# Zio_nRF52832_Dev_Board_V1_0.net
KiCad netlist of a schematic drawn in EAGLE
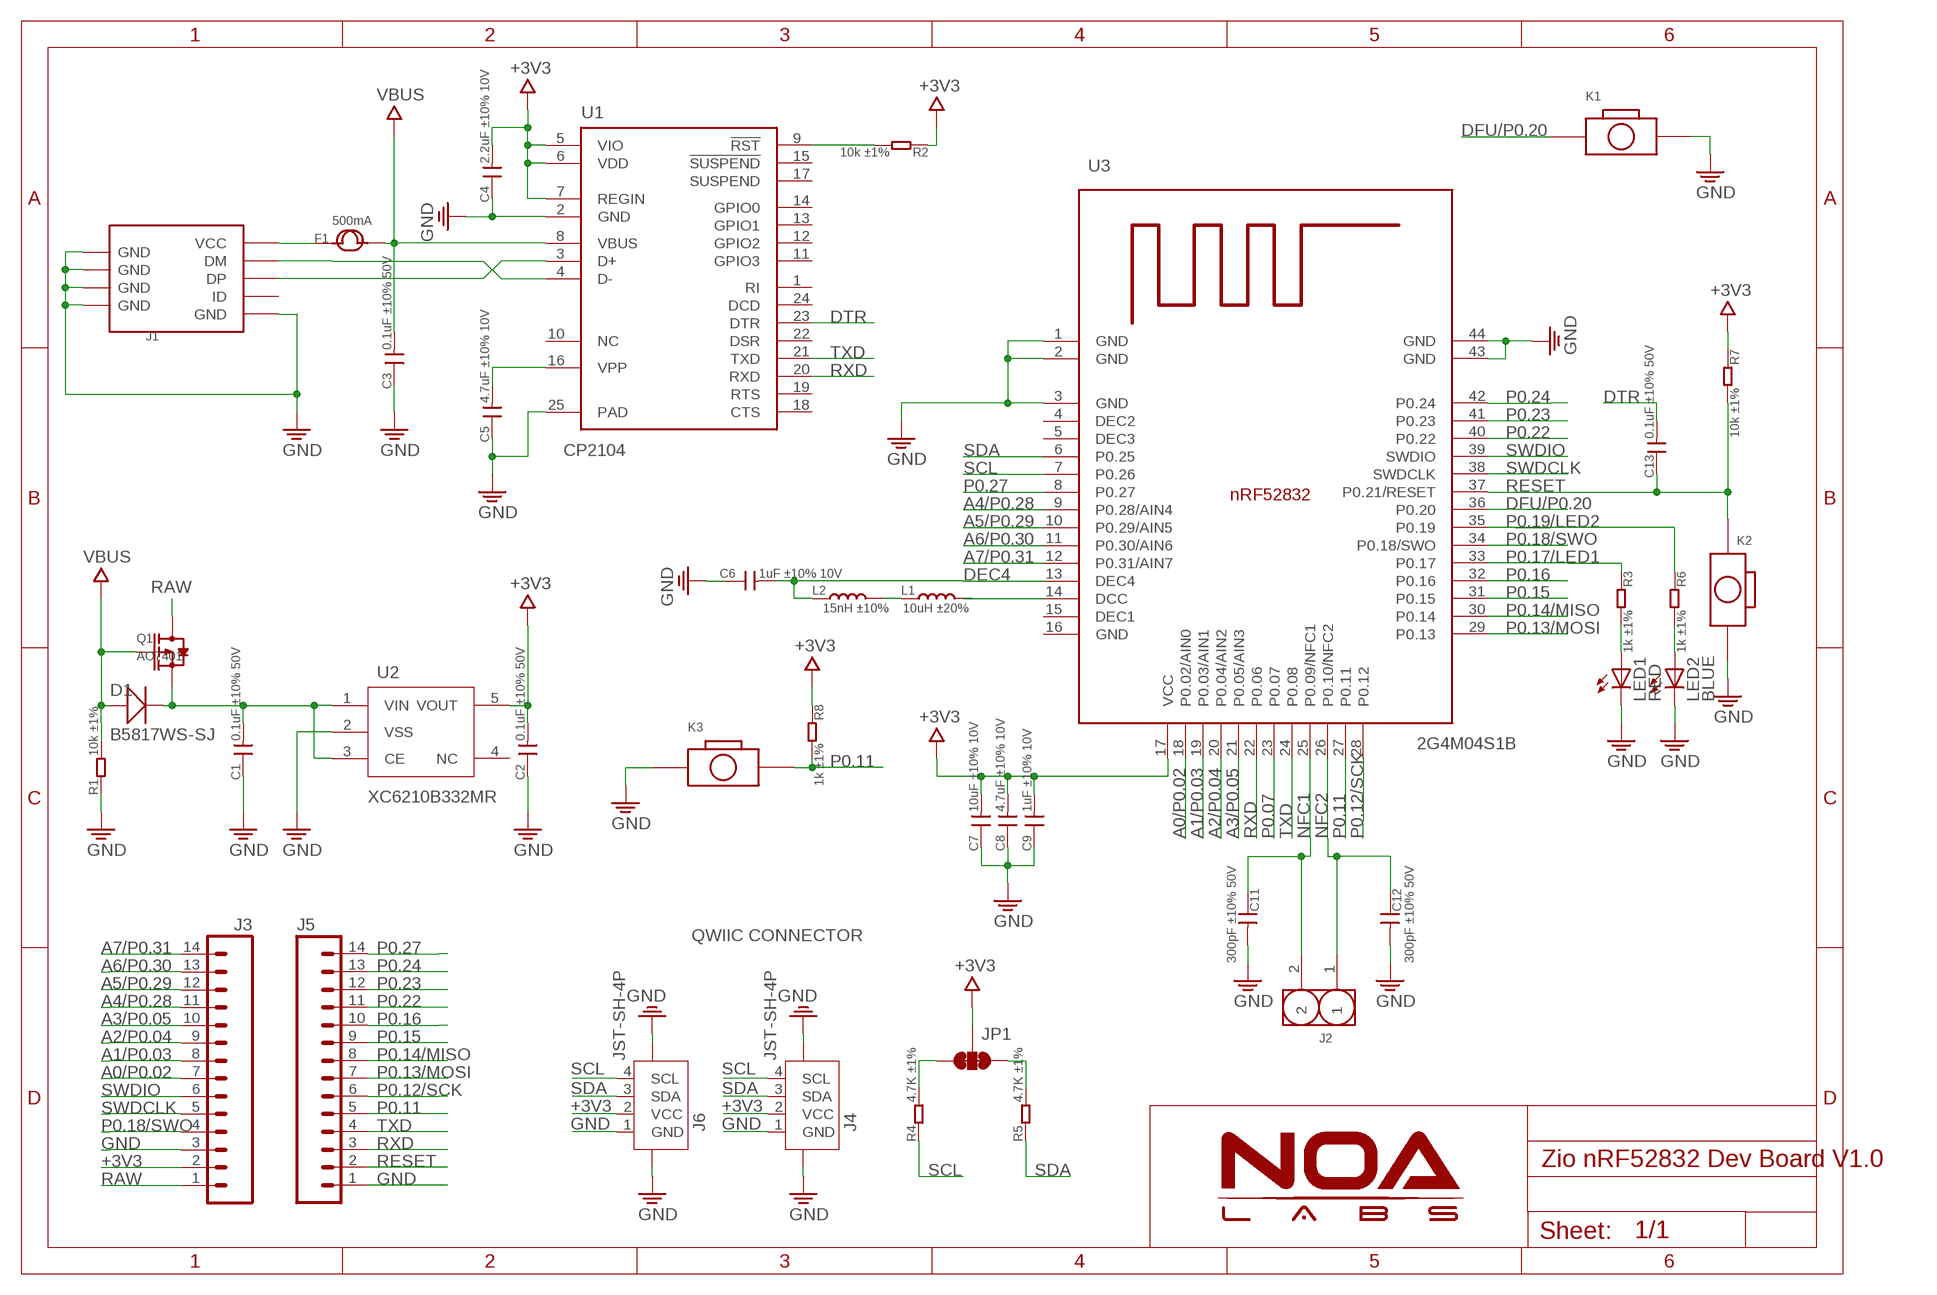
[diagram p0: schematic, sheet 1]

(export (version "E")
  (design (tool "Eeschema 10.0.6"))
  (components
    (comp (ref "C1")
      (value "0.1uF ±10% 50V")
      (footprint "eagle-import:C0603")
      (libsource (lib "eagle-import") (part "C-0603"))
    )
    (comp (ref "C2")
      (value "0.1uF ±10% 50V")
      (footprint "eagle-import:C0603")
      (libsource (lib "eagle-import") (part "C-0603"))
    )
    (comp (ref "C3")
      (value "0.1uF ±10% 50V")
      (footprint "eagle-import:C0603")
      (libsource (lib "eagle-import") (part "C-0603"))
    )
    (comp (ref "C4")
      (value "2.2uF ±10% 10V")
      (footprint "eagle-import:C0603")
      (libsource (lib "eagle-import") (part "C-0603"))
    )
    (comp (ref "C5")
      (value "4.7uF ±10% 10V")
      (footprint "eagle-import:C0603")
      (libsource (lib "eagle-import") (part "C-0603"))
    )
    (comp (ref "C6")
      (value "1uF ±10% 10V")
      (footprint "eagle-import:C0603")
      (libsource (lib "eagle-import") (part "C-0603"))
    )
    (comp (ref "C7")
      (value "10uF ±10% 10V")
      (footprint "eagle-import:C0603")
      (libsource (lib "eagle-import") (part "C-0603"))
    )
    (comp (ref "C8")
      (value "4.7uF ±10% 10V")
      (footprint "eagle-import:C0603")
      (libsource (lib "eagle-import") (part "C-0603"))
    )
    (comp (ref "C9")
      (value "1uF ±10% 10V")
      (footprint "eagle-import:C0603")
      (libsource (lib "eagle-import") (part "C-0603"))
    )
    (comp (ref "C11")
      (value "300pF ±10% 50V")
      (footprint "eagle-import:C0603")
      (libsource (lib "eagle-import") (part "C-0603"))
    )
    (comp (ref "C12")
      (value "300pF ±10% 50V")
      (footprint "eagle-import:C0603")
      (libsource (lib "eagle-import") (part "C-0603"))
    )
    (comp (ref "C13")
      (value "0.1uF ±10% 50V")
      (footprint "eagle-import:C0603")
      (libsource (lib "eagle-import") (part "C-0603"))
    )
    (comp (ref "D1")
      (value "B5817WS-SJ")
      (footprint "eagle-import:SOD323")
      (libsource (lib "eagle-import") (part "D-0805"))
    )
    (comp (ref "F1")
      (value "500mA")
      (footprint "eagle-import:1206")
      (libsource (lib "eagle-import") (part "FUSE1206"))
    )
    (comp (ref "J1")
      (value "USB-MICROE")
      (footprint "eagle-import:MICRO-SMD")
      (libsource (lib "eagle-import") (part "USB-MICROE"))
    )
    (comp (ref "J2")
      (value "HEADER-2P-65/35MIL")
      (footprint "eagle-import:2P-2.54-65_35MIL")
      (libsource (lib "eagle-import") (part "HEADER-2P-65/35MIL"))
    )
    (comp (ref "J3")
      (value "HEADER-14P")
      (footprint "eagle-import:14P-SCREW-2.54")
      (libsource (lib "eagle-import") (part "HEADER-14P"))
    )
    (comp (ref "J4")
      (value "JST-SH-4P")
      (footprint "eagle-import:JST-SH-4P-90")
      (libsource (lib "eagle-import") (part "JST-SH-4P"))
    )
    (comp (ref "J5")
      (value "HEADER-14P")
      (footprint "eagle-import:14P-SCREW-2.54")
      (libsource (lib "eagle-import") (part "HEADER-14P"))
    )
    (comp (ref "J6")
      (value "JST-SH-4P")
      (footprint "eagle-import:JST-SH-4P-90")
      (libsource (lib "eagle-import") (part "JST-SH-4P"))
    )
    (comp (ref "JP1")
      (value "SMT-JUMPER_3_2-NC_TRACE")
      (footprint "eagle-import:SMT-JUMPER_3_2-NC_TRACE")
      (libsource (lib "eagle-import") (part "SMT-JUMPER_3_2-NC_TRACE"))
    )
    (comp (ref "K1")
      (value "BOTTON-2PSKRKAEE020")
      (footprint "eagle-import:SKRKAEE020")
      (libsource (lib "eagle-import") (part "BOTTON-2PSKRKAEE020"))
    )
    (comp (ref "K2")
      (value "BOTTON-2PSKRKAEE020")
      (footprint "eagle-import:SKRKAEE020")
      (libsource (lib "eagle-import") (part "BOTTON-2PSKRKAEE020"))
    )
    (comp (ref "K3")
      (value "BOTTON-2PSKRKAEE020")
      (footprint "eagle-import:SKRKAEE020")
      (libsource (lib "eagle-import") (part "BOTTON-2PSKRKAEE020"))
    )
    (comp (ref "L1")
      (value "10uH ±20%")
      (footprint "eagle-import:L0603")
      (libsource (lib "eagle-import") (part "L-0603"))
    )
    (comp (ref "L2")
      (value "15nH ±10%")
      (footprint "eagle-import:L0402")
      (libsource (lib "eagle-import") (part "L-0402"))
    )
    (comp (ref "LED1")
      (value "RED")
      (footprint "eagle-import:CHIPLED_0603")
      (libsource (lib "eagle-import") (part "LEDCHIPLED_0603"))
    )
    (comp (ref "LED2")
      (value "BLUE")
      (footprint "eagle-import:CHIPLED_0603")
      (libsource (lib "eagle-import") (part "LEDCHIPLED_0603"))
    )
    (comp (ref "Q1")
      (value "AO7401")
      (footprint "eagle-import:SOT-323")
      (libsource (lib "eagle-import") (part "MOSFET-P-323"))
    )
    (comp (ref "R1")
      (value "10k ±1%")
      (footprint "eagle-import:R0603")
      (libsource (lib "eagle-import") (part "R-0603"))
    )
    (comp (ref "R2")
      (value "10k ±1%")
      (footprint "eagle-import:R0603")
      (libsource (lib "eagle-import") (part "R-0603"))
    )
    (comp (ref "R3")
      (value "1k ±1%")
      (footprint "eagle-import:R0603")
      (libsource (lib "eagle-import") (part "R-0603"))
    )
    (comp (ref "R4")
      (value "4.7K ±1%")
      (footprint "eagle-import:R0603")
      (libsource (lib "eagle-import") (part "R-0603"))
    )
    (comp (ref "R5")
      (value "4.7K ±1%")
      (footprint "eagle-import:R0603")
      (libsource (lib "eagle-import") (part "R-0603"))
    )
    (comp (ref "R6")
      (value "1k ±1%")
      (footprint "eagle-import:R0603")
      (libsource (lib "eagle-import") (part "R-0603"))
    )
    (comp (ref "R7")
      (value "10k ±1%")
      (footprint "eagle-import:R0603")
      (libsource (lib "eagle-import") (part "R-0603"))
    )
    (comp (ref "R8")
      (value "1k ±1%")
      (footprint "eagle-import:R0603")
      (libsource (lib "eagle-import") (part "R-0603"))
    )
    (comp (ref "U1")
      (value "CP2104")
      (footprint "eagle-import:QFN24_4X4")
      (libsource (lib "eagle-import") (part "CP2104"))
    )
    (comp (ref "U2")
      (value "XC6210B332MR")
      (footprint "eagle-import:SOT23-5")
      (libsource (lib "eagle-import") (part "XC6210"))
    )
    (comp (ref "U3")
      (value "2G4M04S1B")
      (footprint "eagle-import:2G4M04S1B_NRF52832")
      (libsource (lib "eagle-import") (part "2G4M04S1B_NRF52832"))
    )
  )
  (nets
    (net (code "1") (name "+3V3") (class "Default")
      (node (ref "C2") (pin "2") (pinfunction "2_2") (pintype "passive"))
      (node (ref "C4") (pin "2") (pinfunction "2_2") (pintype "passive"))
      (node (ref "C7") (pin "2") (pinfunction "2_2") (pintype "passive"))
      (node (ref "C8") (pin "2") (pinfunction "2_2") (pintype "passive"))
      (node (ref "C9") (pin "2") (pinfunction "2_2") (pintype "passive"))
      (node (ref "J3") (pin "2") (pinfunction "2_2") (pintype "passive"))
      (node (ref "J4") (pin "2") (pinfunction "VCC_2") (pintype "bidirectional"))
      (node (ref "J6") (pin "2") (pinfunction "VCC_2") (pintype "bidirectional"))
      (node (ref "JP1") (pin "2") (pinfunction "2_2") (pintype "passive"))
      (node (ref "R2") (pin "1") (pinfunction "1_1") (pintype "passive"))
      (node (ref "R7") (pin "1") (pinfunction "1_1") (pintype "passive"))
      (node (ref "R8") (pin "1") (pinfunction "1_1") (pintype "passive"))
      (node (ref "U1") (pin "5") (pinfunction "VIO_5") (pintype "bidirectional"))
      (node (ref "U1") (pin "6") (pinfunction "VDD_6") (pintype "bidirectional"))
      (node (ref "U1") (pin "7") (pinfunction "REGIN_7") (pintype "bidirectional"))
      (node (ref "U2") (pin "5") (pinfunction "VOUT_5") (pintype "bidirectional"))
      (node (ref "U3") (pin "17") (pinfunction "VCC_17") (pintype "bidirectional"))
    )
    (net (code "2") (name "/A0{slash}P0.02") (class "Default")
      (node (ref "J3") (pin "7") (pinfunction "7_7") (pintype "passive"))
      (node (ref "U3") (pin "18") (pinfunction "P0.02/AIN0_18") (pintype "bidirectional"))
    )
    (net (code "3") (name "/A1{slash}P0.03") (class "Default")
      (node (ref "J3") (pin "8") (pinfunction "8_8") (pintype "passive"))
      (node (ref "U3") (pin "19") (pinfunction "P0.03/AIN1_19") (pintype "bidirectional"))
    )
    (net (code "4") (name "/A2{slash}P0.04") (class "Default")
      (node (ref "J3") (pin "9") (pinfunction "9_9") (pintype "passive"))
      (node (ref "U3") (pin "20") (pinfunction "P0.04/AIN2_20") (pintype "bidirectional"))
    )
    (net (code "5") (name "/A3{slash}P0.05") (class "Default")
      (node (ref "J3") (pin "10") (pinfunction "10_10") (pintype "passive"))
      (node (ref "U3") (pin "21") (pinfunction "P0.05/AIN3_21") (pintype "bidirectional"))
    )
    (net (code "6") (name "/A4{slash}P0.28") (class "Default")
      (node (ref "J3") (pin "11") (pinfunction "11_11") (pintype "passive"))
      (node (ref "U3") (pin "9") (pinfunction "P0.28/AIN4_9") (pintype "bidirectional"))
    )
    (net (code "7") (name "/A5{slash}P0.29") (class "Default")
      (node (ref "J3") (pin "12") (pinfunction "12_12") (pintype "passive"))
      (node (ref "U3") (pin "10") (pinfunction "P0.29/AIN5_10") (pintype "bidirectional"))
    )
    (net (code "8") (name "/A6{slash}P0.30") (class "Default")
      (node (ref "J3") (pin "13") (pinfunction "13_13") (pintype "passive"))
      (node (ref "U3") (pin "11") (pinfunction "P0.30/AIN6_11") (pintype "bidirectional"))
    )
    (net (code "9") (name "/A7{slash}P0.31") (class "Default")
      (node (ref "J3") (pin "14") (pinfunction "14_14") (pintype "passive"))
      (node (ref "U3") (pin "12") (pinfunction "P0.31/AIN7_12") (pintype "bidirectional"))
    )
    (net (code "10") (name "/DEC4") (class "Default")
      (node (ref "C6") (pin "2") (pinfunction "2_2") (pintype "passive"))
      (node (ref "L2") (pin "1") (pinfunction "1_1") (pintype "passive"))
      (node (ref "U3") (pin "13") (pinfunction "DEC4_13") (pintype "bidirectional"))
    )
    (net (code "11") (name "/DFU{slash}P0.20") (class "Default")
      (node (ref "K1") (pin "1") (pinfunction "1_1") (pintype "bidirectional"))
      (node (ref "U3") (pin "36") (pinfunction "P0.20_36") (pintype "bidirectional"))
    )
    (net (code "12") (name "/DTR") (class "Default")
      (node (ref "C13") (pin "2") (pinfunction "2_2") (pintype "passive"))
      (node (ref "U1") (pin "23") (pinfunction "DTR_23") (pintype "bidirectional"))
    )
    (net (code "13") (name "/NFC1") (class "Default")
      (node (ref "C11") (pin "1") (pinfunction "1_1") (pintype "passive"))
      (node (ref "J2") (pin "2") (pinfunction "2_2") (pintype "bidirectional"))
      (node (ref "U3") (pin "25") (pinfunction "P0.09/NFC1_25") (pintype "bidirectional"))
    )
    (net (code "14") (name "/NFC2") (class "Default")
      (node (ref "C12") (pin "1") (pinfunction "1_1") (pintype "passive"))
      (node (ref "J2") (pin "1") (pinfunction "1_1") (pintype "bidirectional"))
      (node (ref "U3") (pin "26") (pinfunction "P0.10/NFC2_26") (pintype "bidirectional"))
    )
    (net (code "15") (name "/P0.07") (class "Default")
      (node (ref "U3") (pin "23") (pinfunction "P0.07_23") (pintype "bidirectional"))
    )
    (net (code "16") (name "/P0.11") (class "Default")
      (node (ref "J5") (pin "5") (pinfunction "5_5") (pintype "passive"))
      (node (ref "K3") (pin "2") (pinfunction "2_2") (pintype "bidirectional"))
      (node (ref "R8") (pin "2") (pinfunction "2_2") (pintype "passive"))
      (node (ref "U3") (pin "27") (pinfunction "P0.11_27") (pintype "bidirectional"))
    )
    (net (code "17") (name "/P0.12{slash}SCK") (class "Default")
      (node (ref "J5") (pin "6") (pinfunction "6_6") (pintype "passive"))
      (node (ref "U3") (pin "28") (pinfunction "P0.12_28") (pintype "bidirectional"))
    )
    (net (code "18") (name "/P0.13{slash}MOSI") (class "Default")
      (node (ref "J5") (pin "7") (pinfunction "7_7") (pintype "passive"))
      (node (ref "U3") (pin "29") (pinfunction "P0.13_29") (pintype "bidirectional"))
    )
    (net (code "19") (name "/P0.14{slash}MISO") (class "Default")
      (node (ref "J5") (pin "8") (pinfunction "8_8") (pintype "passive"))
      (node (ref "U3") (pin "30") (pinfunction "P0.14_30") (pintype "bidirectional"))
    )
    (net (code "20") (name "/P0.15") (class "Default")
      (node (ref "J5") (pin "9") (pinfunction "9_9") (pintype "passive"))
      (node (ref "U3") (pin "31") (pinfunction "P0.15_31") (pintype "bidirectional"))
    )
    (net (code "21") (name "/P0.16") (class "Default")
      (node (ref "J5") (pin "10") (pinfunction "10_10") (pintype "passive"))
      (node (ref "U3") (pin "32") (pinfunction "P0.16_32") (pintype "bidirectional"))
    )
    (net (code "22") (name "/P0.17{slash}LED1") (class "Default")
      (node (ref "R3") (pin "1") (pinfunction "1_1") (pintype "passive"))
      (node (ref "U3") (pin "33") (pinfunction "P0.17_33") (pintype "bidirectional"))
    )
    (net (code "23") (name "/P0.18{slash}SWO") (class "Default")
      (node (ref "J3") (pin "4") (pinfunction "4_4") (pintype "passive"))
      (node (ref "U3") (pin "34") (pinfunction "P0.18/SWO_34") (pintype "bidirectional"))
    )
    (net (code "24") (name "/P0.19{slash}LED2") (class "Default")
      (node (ref "R6") (pin "1") (pinfunction "1_1") (pintype "passive"))
      (node (ref "U3") (pin "35") (pinfunction "P0.19_35") (pintype "bidirectional"))
    )
    (net (code "25") (name "/P0.22") (class "Default")
      (node (ref "J5") (pin "11") (pinfunction "11_11") (pintype "passive"))
      (node (ref "U3") (pin "40") (pinfunction "P0.22_40") (pintype "bidirectional"))
    )
    (net (code "26") (name "/P0.23") (class "Default")
      (node (ref "J5") (pin "12") (pinfunction "12_12") (pintype "passive"))
      (node (ref "U3") (pin "41") (pinfunction "P0.23_41") (pintype "bidirectional"))
    )
    (net (code "27") (name "/P0.24") (class "Default")
      (node (ref "J5") (pin "13") (pinfunction "13_13") (pintype "passive"))
      (node (ref "U3") (pin "42") (pinfunction "P0.24_42") (pintype "bidirectional"))
    )
    (net (code "28") (name "/P0.27") (class "Default")
      (node (ref "J5") (pin "14") (pinfunction "14_14") (pintype "passive"))
      (node (ref "U3") (pin "8") (pinfunction "P0.27_8") (pintype "bidirectional"))
    )
    (net (code "29") (name "/RAW") (class "Default")
      (node (ref "J3") (pin "1") (pinfunction "1_1") (pintype "passive"))
      (node (ref "Q1") (pin "3") (pinfunction "D_3") (pintype "passive"))
    )
    (net (code "30") (name "/RESET") (class "Default")
      (node (ref "C13") (pin "1") (pinfunction "1_1") (pintype "passive"))
      (node (ref "J5") (pin "2") (pinfunction "2_2") (pintype "passive"))
      (node (ref "K2") (pin "1") (pinfunction "1_1") (pintype "bidirectional"))
      (node (ref "R7") (pin "2") (pinfunction "2_2") (pintype "passive"))
      (node (ref "U3") (pin "37") (pinfunction "P0.21/RESET_37") (pintype "bidirectional"))
    )
    (net (code "31") (name "/RXD") (class "Default")
      (node (ref "J5") (pin "3") (pinfunction "3_3") (pintype "passive"))
      (node (ref "U1") (pin "20") (pinfunction "RXD_20") (pintype "bidirectional"))
      (node (ref "U3") (pin "22") (pinfunction "P0.06_22") (pintype "bidirectional"))
    )
    (net (code "32") (name "/SCL") (class "Default")
      (node (ref "J4") (pin "4") (pinfunction "SCL_4") (pintype "bidirectional"))
      (node (ref "J6") (pin "4") (pinfunction "SCL_4") (pintype "bidirectional"))
      (node (ref "R4") (pin "1") (pinfunction "1_1") (pintype "passive"))
      (node (ref "U3") (pin "7") (pinfunction "P0.26_7") (pintype "bidirectional"))
    )
    (net (code "33") (name "/SDA") (class "Default")
      (node (ref "J4") (pin "3") (pinfunction "SDA_3") (pintype "bidirectional"))
      (node (ref "J6") (pin "3") (pinfunction "SDA_3") (pintype "bidirectional"))
      (node (ref "R5") (pin "1") (pinfunction "1_1") (pintype "passive"))
      (node (ref "U3") (pin "6") (pinfunction "P0.25_6") (pintype "bidirectional"))
    )
    (net (code "34") (name "/SWDCLK") (class "Default")
      (node (ref "J3") (pin "5") (pinfunction "5_5") (pintype "passive"))
      (node (ref "U3") (pin "38") (pinfunction "SWDCLK_38") (pintype "bidirectional"))
    )
    (net (code "35") (name "/SWDIO") (class "Default")
      (node (ref "J3") (pin "6") (pinfunction "6_6") (pintype "passive"))
      (node (ref "U3") (pin "39") (pinfunction "SWDIO_39") (pintype "bidirectional"))
    )
    (net (code "36") (name "/TXD") (class "Default")
      (node (ref "J5") (pin "4") (pinfunction "4_4") (pintype "passive"))
      (node (ref "U1") (pin "21") (pinfunction "TXD_21") (pintype "bidirectional"))
      (node (ref "U3") (pin "24") (pinfunction "P0.08_24") (pintype "bidirectional"))
    )
    (net (code "37") (name "GND") (class "Default")
      (node (ref "C1") (pin "1") (pinfunction "1_1") (pintype "passive"))
      (node (ref "C11") (pin "2") (pinfunction "2_2") (pintype "passive"))
      (node (ref "C12") (pin "2") (pinfunction "2_2") (pintype "passive"))
      (node (ref "C2") (pin "1") (pinfunction "1_1") (pintype "passive"))
      (node (ref "C3") (pin "1") (pinfunction "1_1") (pintype "passive"))
      (node (ref "C4") (pin "1") (pinfunction "1_1") (pintype "passive"))
      (node (ref "C5") (pin "1") (pinfunction "1_1") (pintype "passive"))
      (node (ref "C6") (pin "1") (pinfunction "1_1") (pintype "passive"))
      (node (ref "C7") (pin "1") (pinfunction "1_1") (pintype "passive"))
      (node (ref "C8") (pin "1") (pinfunction "1_1") (pintype "passive"))
      (node (ref "C9") (pin "1") (pinfunction "1_1") (pintype "passive"))
      (node (ref "J1") (pin "P5") (pinfunction "GND_P5") (pintype "bidirectional"))
      (node (ref "J1") (pin "S1") (pinfunction "GND_S1") (pintype "bidirectional"))
      (node (ref "J1") (pin "S2") (pinfunction "GND_S2") (pintype "bidirectional"))
      (node (ref "J1") (pin "S3") (pinfunction "GND_S3") (pintype "bidirectional"))
      (node (ref "J1") (pin "S4") (pinfunction "GND_S4") (pintype "bidirectional"))
      (node (ref "J3") (pin "3") (pinfunction "3_3") (pintype "passive"))
      (node (ref "J4") (pin "1") (pinfunction "GND_1") (pintype "bidirectional"))
      (node (ref "J4") (pin "5") (pinfunction "5_5") (pintype "bidirectional"))
      (node (ref "J4") (pin "6") (pinfunction "6_6") (pintype "bidirectional"))
      (node (ref "J5") (pin "1") (pinfunction "1_1") (pintype "passive"))
      (node (ref "J6") (pin "1") (pinfunction "GND_1") (pintype "bidirectional"))
      (node (ref "J6") (pin "5") (pinfunction "5_5") (pintype "bidirectional"))
      (node (ref "J6") (pin "6") (pinfunction "6_6") (pintype "bidirectional"))
      (node (ref "K1") (pin "2") (pinfunction "2_2") (pintype "bidirectional"))
      (node (ref "K2") (pin "2") (pinfunction "2_2") (pintype "bidirectional"))
      (node (ref "K3") (pin "1") (pinfunction "1_1") (pintype "bidirectional"))
      (node (ref "LED1") (pin "C") (pinfunction "C_C") (pintype "passive"))
      (node (ref "LED2") (pin "C") (pinfunction "C_C") (pintype "passive"))
      (node (ref "R1") (pin "1") (pinfunction "1_1") (pintype "passive"))
      (node (ref "U1") (pin "2") (pinfunction "GND_2") (pintype "bidirectional"))
      (node (ref "U1") (pin "25") (pinfunction "PAD_25") (pintype "bidirectional"))
      (node (ref "U2") (pin "2") (pinfunction "VSS_2") (pintype "bidirectional"))
      (node (ref "U3") (pin "1") (pinfunction "GND_1") (pintype "bidirectional"))
      (node (ref "U3") (pin "2") (pinfunction "GND_2") (pintype "bidirectional"))
      (node (ref "U3") (pin "3") (pinfunction "GND_3") (pintype "bidirectional"))
      (node (ref "U3") (pin "43") (pinfunction "GND_43") (pintype "bidirectional"))
      (node (ref "U3") (pin "44") (pinfunction "GND_44") (pintype "bidirectional"))
    )
    (net (code "38") (name "Net-(J1-DM)") (class "Default")
      (node (ref "J1") (pin "P2") (pinfunction "DM_P2") (pintype "bidirectional"))
      (node (ref "U1") (pin "4") (pinfunction "D-_4") (pintype "bidirectional"))
    )
    (net (code "39") (name "Net-(J1-DP)") (class "Default")
      (node (ref "J1") (pin "P3") (pinfunction "DP_P3") (pintype "bidirectional"))
      (node (ref "U1") (pin "3") (pinfunction "D+_3") (pintype "bidirectional"))
    )
    (net (code "40") (name "Net-(J1-VCC)") (class "Default")
      (node (ref "F1") (pin "1") (pinfunction "1_1") (pintype "bidirectional"))
      (node (ref "J1") (pin "P1") (pinfunction "VCC_P1") (pintype "bidirectional"))
    )
    (net (code "41") (name "Net-(JP1-Pad1)") (class "Default")
      (node (ref "JP1") (pin "1") (pinfunction "1_1") (pintype "passive"))
      (node (ref "R5") (pin "2") (pinfunction "2_2") (pintype "passive"))
    )
    (net (code "42") (name "Net-(JP1-Pad3)") (class "Default")
      (node (ref "JP1") (pin "3") (pinfunction "3_3") (pintype "passive"))
      (node (ref "R4") (pin "2") (pinfunction "2_2") (pintype "passive"))
    )
    (net (code "43") (name "Net-(L1-Pad1)") (class "Default")
      (node (ref "L1") (pin "1") (pinfunction "1_1") (pintype "passive"))
      (node (ref "L2") (pin "2") (pinfunction "2_2") (pintype "passive"))
    )
    (net (code "44") (name "Net-(LED1-PadA)") (class "Default")
      (node (ref "LED1") (pin "A") (pinfunction "A_A") (pintype "passive"))
      (node (ref "R3") (pin "2") (pinfunction "2_2") (pintype "passive"))
    )
    (net (code "45") (name "Net-(LED2-PadA)") (class "Default")
      (node (ref "LED2") (pin "A") (pinfunction "A_A") (pintype "passive"))
      (node (ref "R6") (pin "2") (pinfunction "2_2") (pintype "passive"))
    )
    (net (code "46") (name "Net-(Q1-S)") (class "Default")
      (node (ref "C1") (pin "2") (pinfunction "2_2") (pintype "passive"))
      (node (ref "D1") (pin "-") (pinfunction "-_-") (pintype "passive"))
      (node (ref "Q1") (pin "2") (pinfunction "S_2") (pintype "passive"))
      (node (ref "U2") (pin "1") (pinfunction "VIN_1") (pintype "bidirectional"))
      (node (ref "U2") (pin "3") (pinfunction "CE_3") (pintype "bidirectional"))
    )
    (net (code "47") (name "Net-(U1-VPP)") (class "Default")
      (node (ref "C5") (pin "2") (pinfunction "2_2") (pintype "passive"))
      (node (ref "U1") (pin "16") (pinfunction "VPP_16") (pintype "bidirectional"))
    )
    (net (code "48") (name "Net-(U1-~{RST})") (class "Default")
      (node (ref "R2") (pin "2") (pinfunction "2_2") (pintype "passive"))
      (node (ref "U1") (pin "9") (pinfunction "~{RST}_9") (pintype "bidirectional"))
    )
    (net (code "49") (name "Net-(U3-DCC)") (class "Default")
      (node (ref "L1") (pin "2") (pinfunction "2_2") (pintype "passive"))
      (node (ref "U3") (pin "14") (pinfunction "DCC_14") (pintype "bidirectional"))
    )
    (net (code "50") (name "VBUS") (class "Default")
      (node (ref "C3") (pin "2") (pinfunction "2_2") (pintype "passive"))
      (node (ref "D1") (pin "+") (pinfunction "+_+") (pintype "passive"))
      (node (ref "F1") (pin "2") (pinfunction "2_2") (pintype "bidirectional"))
      (node (ref "Q1") (pin "1") (pinfunction "G_1") (pintype "passive"))
      (node (ref "R1") (pin "2") (pinfunction "2_2") (pintype "passive"))
      (node (ref "U1") (pin "8") (pinfunction "VBUS_8") (pintype "bidirectional"))
    )
    (net (code "51") (name "unconnected-(J1-ID-PadP4)") (class "Default")
      (node (ref "J1") (pin "P4") (pinfunction "ID_P4") (pintype "bidirectional"))
    )
    (net (code "52") (name "unconnected-(U1-CTS-Pad18)") (class "Default")
      (node (ref "U1") (pin "18") (pinfunction "CTS_18") (pintype "bidirectional"))
    )
    (net (code "53") (name "unconnected-(U1-DCD-Pad24)") (class "Default")
      (node (ref "U1") (pin "24") (pinfunction "DCD_24") (pintype "bidirectional"))
    )
    (net (code "54") (name "unconnected-(U1-DSR-Pad22)") (class "Default")
      (node (ref "U1") (pin "22") (pinfunction "DSR_22") (pintype "bidirectional"))
    )
    (net (code "55") (name "unconnected-(U1-GPIO0-Pad14)") (class "Default")
      (node (ref "U1") (pin "14") (pinfunction "GPIO0_14") (pintype "bidirectional"))
    )
    (net (code "56") (name "unconnected-(U1-GPIO1-Pad13)") (class "Default")
      (node (ref "U1") (pin "13") (pinfunction "GPIO1_13") (pintype "bidirectional"))
    )
    (net (code "57") (name "unconnected-(U1-GPIO2-Pad12)") (class "Default")
      (node (ref "U1") (pin "12") (pinfunction "GPIO2_12") (pintype "bidirectional"))
    )
    (net (code "58") (name "unconnected-(U1-GPIO3-Pad11)") (class "Default")
      (node (ref "U1") (pin "11") (pinfunction "GPIO3_11") (pintype "bidirectional"))
    )
    (net (code "59") (name "unconnected-(U1-NC-Pad10)") (class "Default")
      (node (ref "U1") (pin "10") (pinfunction "NC_10") (pintype "bidirectional"))
    )
    (net (code "60") (name "unconnected-(U1-RI-Pad1)") (class "Default")
      (node (ref "U1") (pin "1") (pinfunction "RI_1") (pintype "bidirectional"))
    )
    (net (code "61") (name "unconnected-(U1-RTS-Pad19)") (class "Default")
      (node (ref "U1") (pin "19") (pinfunction "RTS_19") (pintype "bidirectional"))
    )
    (net (code "62") (name "unconnected-(U1-SUSPEND-Pad17)") (class "Default")
      (node (ref "U1") (pin "17") (pinfunction "SUSPEND_17") (pintype "bidirectional"))
    )
    (net (code "63") (name "unconnected-(U1-~{SUSPEND}-Pad15)") (class "Default")
      (node (ref "U1") (pin "15") (pinfunction "~{SUSPEND}_15") (pintype "bidirectional"))
    )
    (net (code "64") (name "unconnected-(U2-NC-Pad4)") (class "Default")
      (node (ref "U2") (pin "4") (pinfunction "NC_4") (pintype "bidirectional"))
    )
    (net (code "65") (name "unconnected-(U3-DEC1-Pad15)") (class "Default")
      (node (ref "U3") (pin "15") (pinfunction "DEC1_15") (pintype "bidirectional"))
    )
    (net (code "66") (name "unconnected-(U3-DEC2-Pad4)") (class "Default")
      (node (ref "U3") (pin "4") (pinfunction "DEC2_4") (pintype "bidirectional"))
    )
    (net (code "67") (name "unconnected-(U3-DEC3-Pad5)") (class "Default")
      (node (ref "U3") (pin "5") (pinfunction "DEC3_5") (pintype "bidirectional"))
    )
    (net (code "68") (name "unconnected-(U3-GND-Pad16)") (class "Default")
      (node (ref "U3") (pin "16") (pinfunction "GND_16") (pintype "bidirectional"))
    )
  )
)
